# DAC_breakout.net
KiCad netlist of a schematic drawn in EAGLE
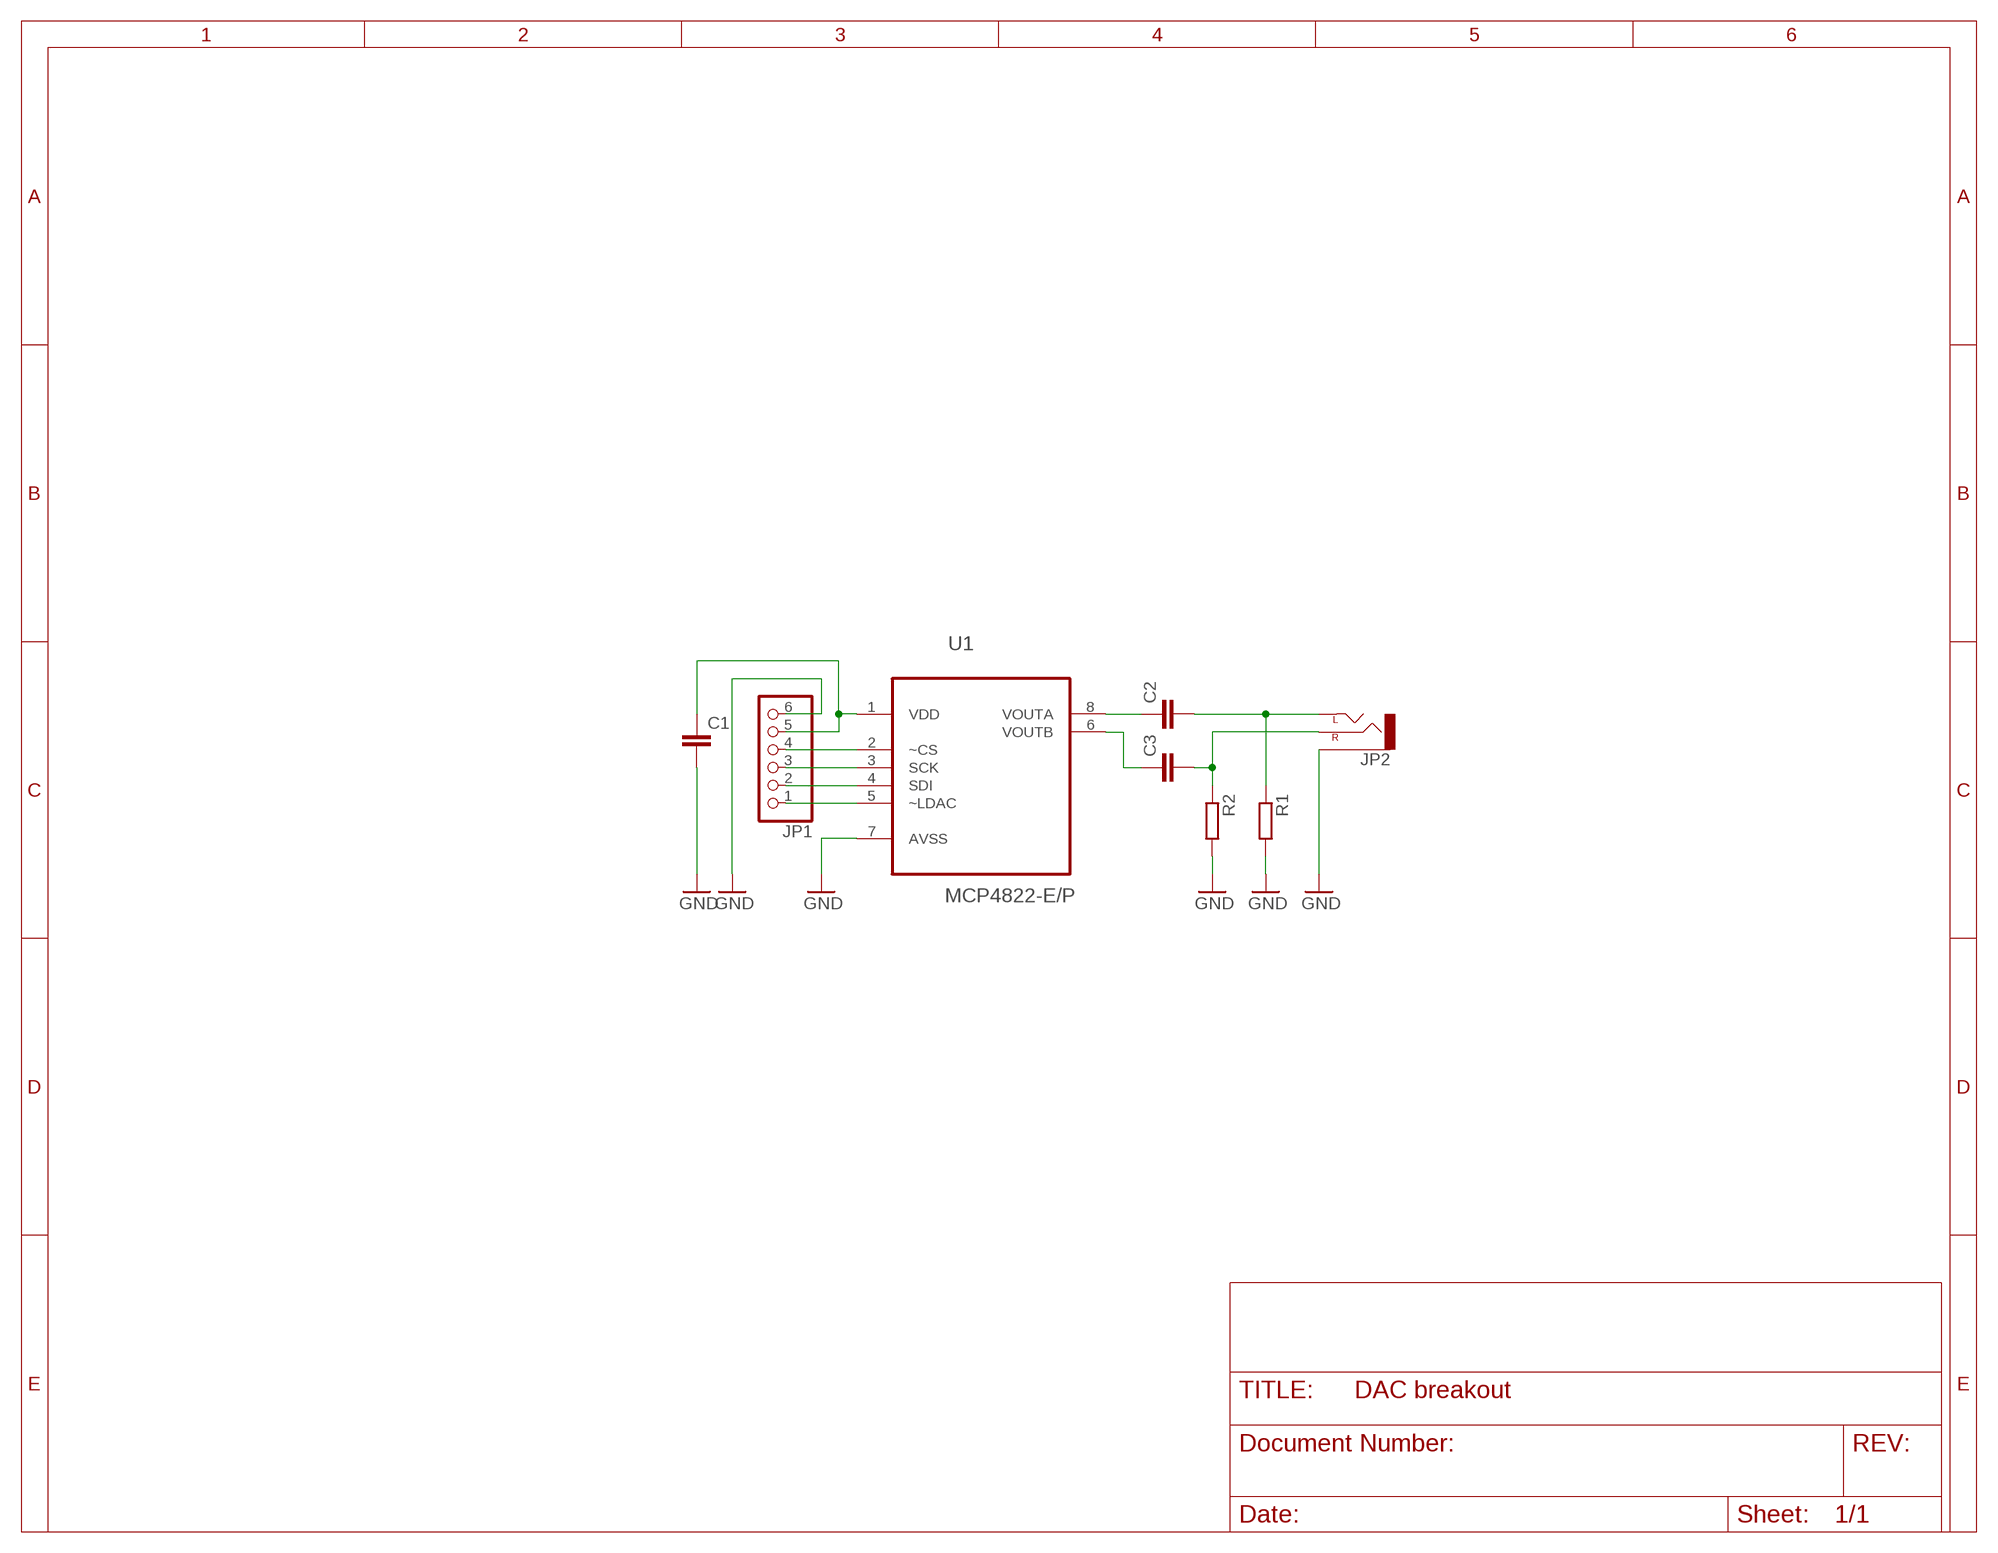
[diagram p0: schematic, sheet 1]

(export (version "E")
  (design (tool "Eeschema 10.0.6"))
  (components
    (comp (ref "C1")
      (value "C5/3")
      (footprint "eagle-import:C5B3")
      (libsource (lib "eagle-import") (part "C5/3"))
    )
    (comp (ref "C2")
      (value "C5/3")
      (footprint "eagle-import:C5B3")
      (libsource (lib "eagle-import") (part "C5/3"))
    )
    (comp (ref "C3")
      (value "C5/3")
      (footprint "eagle-import:C5B3")
      (libsource (lib "eagle-import") (part "C5/3"))
    )
    (comp (ref "JP1")
      (value "PINHD-1X6")
      (footprint "eagle-import:1X06")
      (libsource (lib "eagle-import") (part "PINHD-1X6"))
    )
    (comp (ref "JP2")
      (value "AUDIO-JACKPTH")
      (footprint "eagle-import:AUDIO-JACK")
      (libsource (lib "eagle-import") (part "AUDIO-JACKPTH"))
    )
    (comp (ref "R1")
      (value "R-EU_0204/7")
      (footprint "eagle-import:0204_7")
      (libsource (lib "eagle-import") (part "R-EU_0204/7"))
    )
    (comp (ref "R2")
      (value "R-EU_0204/7")
      (footprint "eagle-import:0204_7")
      (libsource (lib "eagle-import") (part "R-EU_0204/7"))
    )
    (comp (ref "U1")
      (value "MCP4822-E/P")
      (footprint "eagle-import:DIP254P762X432-8")
      (libsource (lib "eagle-import") (part "MCP4822-E/P"))
    )
  )
  (nets
    (net (code "1") (name "GND") (class "Default")
      (node (ref "C1") (pin "2") (pinfunction "2_2") (pintype "passive"))
      (node (ref "JP1") (pin "6") (pinfunction "6_6") (pintype "passive"))
      (node (ref "JP2") (pin "SLEEVE") (pinfunction "SLEEVE_SLEEVE") (pintype "bidirectional"))
      (node (ref "R1") (pin "2") (pinfunction "2_2") (pintype "passive"))
      (node (ref "R2") (pin "2") (pinfunction "2_2") (pintype "passive"))
      (node (ref "U1") (pin "7") (pinfunction "AVSS_7") (pintype "passive"))
    )
    (net (code "2") (name "Net-(JP2-LEFT)") (class "Default")
      (node (ref "C2") (pin "2") (pinfunction "2_2") (pintype "passive"))
      (node (ref "JP2") (pin "TIP") (pinfunction "LEFT_TIP") (pintype "bidirectional"))
      (node (ref "R1") (pin "1") (pinfunction "1_1") (pintype "passive"))
    )
    (net (code "3") (name "Net-(JP2-RIGHT)") (class "Default")
      (node (ref "C3") (pin "2") (pinfunction "2_2") (pintype "passive"))
      (node (ref "JP2") (pin "RING") (pinfunction "RIGHT_RING") (pintype "bidirectional"))
      (node (ref "R2") (pin "1") (pinfunction "1_1") (pintype "passive"))
    )
    (net (code "4") (name "Net-(U1-SCK)") (class "Default")
      (node (ref "JP1") (pin "3") (pinfunction "3_3") (pintype "passive"))
      (node (ref "U1") (pin "3") (pinfunction "SCK_3") (pintype "input"))
    )
    (net (code "5") (name "Net-(U1-SDI)") (class "Default")
      (node (ref "JP1") (pin "2") (pinfunction "2_2") (pintype "passive"))
      (node (ref "U1") (pin "4") (pinfunction "SDI_4") (pintype "input"))
    )
    (net (code "6") (name "Net-(U1-VDD)") (class "Default")
      (node (ref "C1") (pin "1") (pinfunction "1_1") (pintype "passive"))
      (node (ref "JP1") (pin "5") (pinfunction "5_5") (pintype "passive"))
      (node (ref "U1") (pin "1") (pinfunction "VDD_1") (pintype "power_in"))
    )
    (net (code "7") (name "Net-(U1-VOUTA)") (class "Default")
      (node (ref "C2") (pin "1") (pinfunction "1_1") (pintype "passive"))
      (node (ref "U1") (pin "8") (pinfunction "VOUTA_8") (pintype "output"))
    )
    (net (code "8") (name "Net-(U1-VOUTB)") (class "Default")
      (node (ref "C3") (pin "1") (pinfunction "1_1") (pintype "passive"))
      (node (ref "U1") (pin "6") (pinfunction "VOUTB_6") (pintype "output"))
    )
    (net (code "9") (name "Net-(U1-~{CS})") (class "Default")
      (node (ref "JP1") (pin "4") (pinfunction "4_4") (pintype "passive"))
      (node (ref "U1") (pin "2") (pinfunction "~{CS}_2") (pintype "input"))
    )
    (net (code "10") (name "Net-(U1-~{LDAC})") (class "Default")
      (node (ref "JP1") (pin "1") (pinfunction "1_1") (pintype "passive"))
      (node (ref "U1") (pin "5") (pinfunction "~{LDAC}_5") (pintype "input"))
    )
  )
)
